# CD40106-4069-Synth.net
KiCad netlist of a schematic drawn in EAGLE
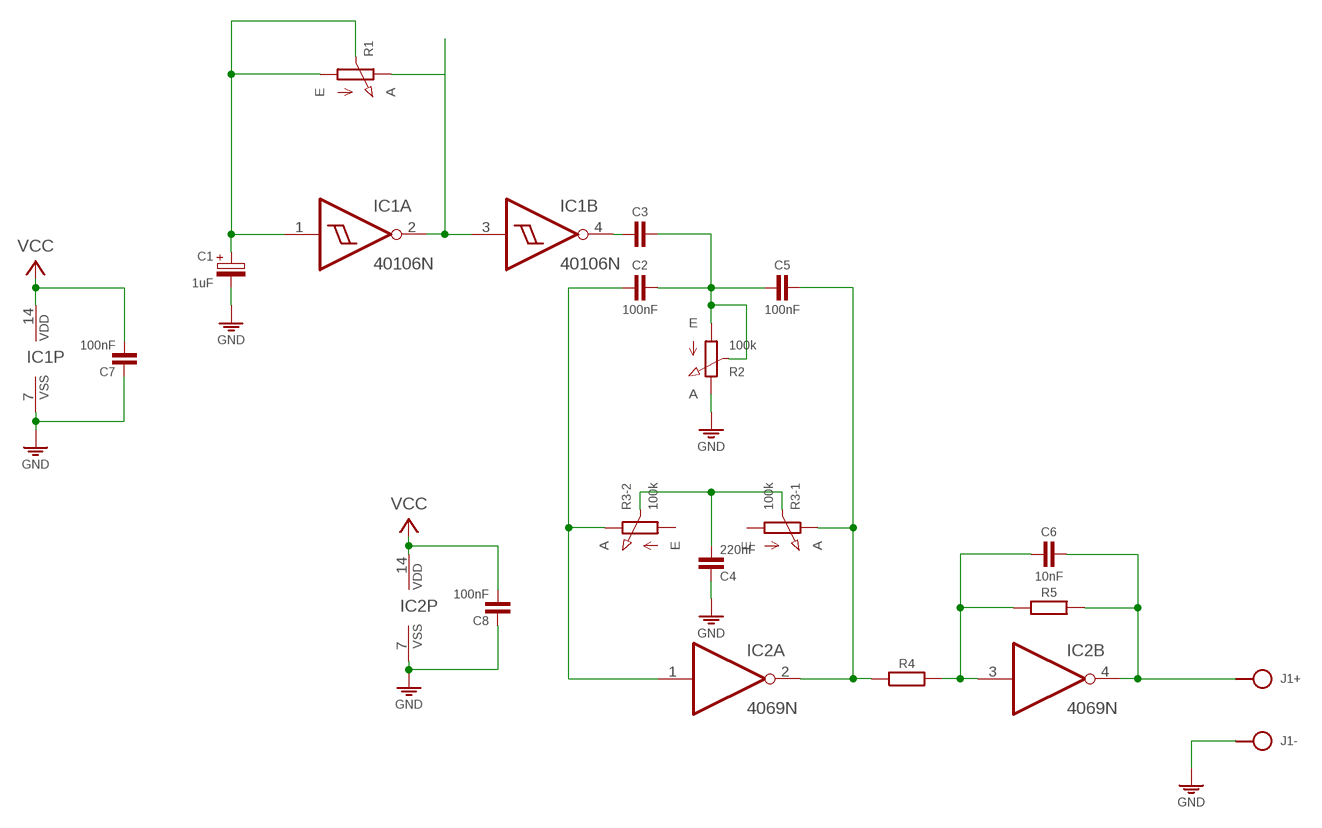
[diagram p0: schematic, sheet 1]

(export (version "E")
  (design (tool "Eeschema 10.0.6"))
  (components
    (comp (ref "C1")
      (value "1uF")
      (footprint "eagle-import:E2.5-4_V")
      (libsource (lib "eagle-import") (part "CPOLE2,5-4/V"))
    )
    (comp (ref "C2")
      (value "100nF")
      (footprint "eagle-import:C050-020X044")
      (libsource (lib "eagle-import") (part "C-H050-020X044"))
    )
    (comp (ref "C3")
      (value "C-H050-020X044")
      (footprint "eagle-import:C050-020X044")
      (libsource (lib "eagle-import") (part "C-H050-020X044"))
    )
    (comp (ref "C4")
      (value "220nF")
      (footprint "eagle-import:C050-020X044_V")
      (libsource (lib "eagle-import") (part "C050-020X044/V"))
    )
    (comp (ref "C5")
      (value "100nF")
      (footprint "eagle-import:C050-020X044")
      (libsource (lib "eagle-import") (part "C-H050-020X044"))
    )
    (comp (ref "C6")
      (value "10nF")
      (footprint "eagle-import:C050-020X044")
      (libsource (lib "eagle-import") (part "C-H050-020X044"))
    )
    (comp (ref "C7")
      (value "100nF")
      (footprint "eagle-import:C050-020X044_V")
      (libsource (lib "eagle-import") (part "C050-020X044/V"))
    )
    (comp (ref "C8")
      (value "100nF")
      (footprint "eagle-import:C050-020X044_V")
      (libsource (lib "eagle-import") (part "C050-020X044/V"))
    )
    (comp (ref "IC1")
      (value "40106N")
      (footprint "eagle-import:DIL14")
      (libsource (lib "eagle-import") (part "40106N"))
    )
    (comp (ref "IC2")
      (value "4069N")
      (footprint "eagle-import:DIL14")
      (libsource (lib "eagle-import") (part "4069N"))
    )
    (comp (ref "J1")
      (value "SPAD+-+-")
      (footprint "eagle-import:SPAD+-")
      (libsource (lib "eagle-import") (part "SPAD+-+-"))
    )
    (comp (ref "J2")
      (value "VCC_GNDL")
      (footprint "eagle-import:SPAD-+")
      (libsource (lib "eagle-import") (part "VCC_GNDL"))
    )
    (comp (ref "R1")
      (value "POT")
      (footprint "eagle-import:POT")
      (libsource (lib "eagle-import") (part "POT"))
    )
    (comp (ref "R2")
      (value "100k")
      (footprint "eagle-import:POT")
      (libsource (lib "eagle-import") (part "POT"))
    )
    (comp (ref "R3")
      (value "100k")
      (footprint "eagle-import:POT-STEREO-2X3")
      (libsource (lib "eagle-import") (part "POT-STEREO"))
    )
    (comp (ref "R4")
      (value "R-H0204/2-V")
      (footprint "eagle-import:0204V")
      (libsource (lib "eagle-import") (part "R-H0204/2-V"))
    )
    (comp (ref "R5")
      (value "R-H0204/10-V")
      (footprint "eagle-import:0204_10-V")
      (libsource (lib "eagle-import") (part "R-H0204/10-V"))
    )
  )
  (nets
    (net (code "1") (name "GND") (class "Default")
      (node (ref "C1") (pin "-") (pinfunction "-_-") (pintype "passive"))
      (node (ref "C4") (pin "1") (pinfunction "1_1") (pintype "passive"))
      (node (ref "C7") (pin "1") (pinfunction "1_1") (pintype "passive"))
      (node (ref "C8") (pin "1") (pinfunction "1_1") (pintype "passive"))
      (node (ref "IC1") (pin "7") (pinfunction "VSS_7") (pintype "power_in"))
      (node (ref "IC2") (pin "7") (pinfunction "VSS_7") (pintype "power_in"))
      (node (ref "J1") (pin "1") (pinfunction "P$1_1") (pintype "passive"))
      (node (ref "J2") (pin "1") (pinfunction "GND_1") (pintype "power_in"))
      (node (ref "R2") (pin "3") (pinfunction "E_3") (pintype "passive"))
    )
    (net (code "2") (name "Net-(IC1A-I)") (class "Default")
      (node (ref "C1") (pin "+") (pinfunction "+_+") (pintype "passive"))
      (node (ref "IC1") (pin "1") (pinfunction "I_1") (pintype "input"))
      (node (ref "R1") (pin "1") (pinfunction "A_1") (pintype "passive"))
      (node (ref "R1") (pin "2") (pinfunction "S_2") (pintype "passive"))
    )
    (net (code "3") (name "Net-(IC1A-O)") (class "Default")
      (node (ref "IC1") (pin "2") (pinfunction "O_2") (pintype "output"))
      (node (ref "IC1") (pin "3") (pinfunction "I_3") (pintype "input"))
      (node (ref "R1") (pin "3") (pinfunction "E_3") (pintype "passive"))
    )
    (net (code "4") (name "Net-(IC1B-O)") (class "Default")
      (node (ref "C3") (pin "1") (pinfunction "1_1") (pintype "passive"))
      (node (ref "IC1") (pin "4") (pinfunction "O_4") (pintype "output"))
    )
    (net (code "5") (name "Net-(IC2A-I)") (class "Default")
      (node (ref "C2") (pin "1") (pinfunction "1_1") (pintype "passive"))
      (node (ref "IC2") (pin "1") (pinfunction "I_1") (pintype "input"))
      (node (ref "R3") (pin "2-E") (pinfunction "E_2-E") (pintype "passive"))
    )
    (net (code "6") (name "Net-(IC2A-O)") (class "Default")
      (node (ref "C5") (pin "2") (pinfunction "2_2") (pintype "passive"))
      (node (ref "IC2") (pin "2") (pinfunction "O_2") (pintype "output"))
      (node (ref "R3") (pin "1-E") (pinfunction "E_1-E") (pintype "passive"))
      (node (ref "R4") (pin "1") (pinfunction "1_1") (pintype "passive"))
    )
    (net (code "7") (name "Net-(IC2B-I)") (class "Default")
      (node (ref "C6") (pin "1") (pinfunction "1_1") (pintype "passive"))
      (node (ref "IC2") (pin "3") (pinfunction "I_3") (pintype "input"))
      (node (ref "R4") (pin "2") (pinfunction "2_2") (pintype "passive"))
      (node (ref "R5") (pin "1") (pinfunction "1_1") (pintype "passive"))
    )
    (net (code "8") (name "Net-(IC2B-O)") (class "Default")
      (node (ref "C6") (pin "2") (pinfunction "2_2") (pintype "passive"))
      (node (ref "IC2") (pin "4") (pinfunction "O_4") (pintype "output"))
      (node (ref "J1") (pin "2") (pinfunction "P$1_2") (pintype "passive"))
      (node (ref "R5") (pin "2") (pinfunction "2_2") (pintype "passive"))
    )
    (net (code "9") (name "Net-(R2-A)") (class "Default")
      (node (ref "C2") (pin "2") (pinfunction "2_2") (pintype "passive"))
      (node (ref "C3") (pin "2") (pinfunction "2_2") (pintype "passive"))
      (node (ref "C5") (pin "1") (pinfunction "1_1") (pintype "passive"))
      (node (ref "R2") (pin "1") (pinfunction "A_1") (pintype "passive"))
      (node (ref "R2") (pin "2") (pinfunction "S_2") (pintype "passive"))
    )
    (net (code "10") (name "Net-(R3A-S)") (class "Default")
      (node (ref "C4") (pin "2") (pinfunction "2_2") (pintype "passive"))
      (node (ref "R3") (pin "1-S") (pinfunction "S_1-S") (pintype "passive"))
      (node (ref "R3") (pin "2-S") (pinfunction "S_2-S") (pintype "passive"))
    )
    (net (code "11") (name "VCC") (class "Default")
      (node (ref "C7") (pin "2") (pinfunction "2_2") (pintype "passive"))
      (node (ref "C8") (pin "2") (pinfunction "2_2") (pintype "passive"))
      (node (ref "IC1") (pin "14") (pinfunction "VDD_14") (pintype "power_in"))
      (node (ref "IC2") (pin "14") (pinfunction "VDD_14") (pintype "power_in"))
      (node (ref "J2") (pin "2") (pinfunction "VCC_2") (pintype "power_in"))
    )
    (net (code "12") (name "unconnected-(R3A-A-Pad1-A)") (class "Default")
      (node (ref "R3") (pin "1-A") (pinfunction "A_1-A") (pintype "passive"))
    )
    (net (code "13") (name "unconnected-(R3B-A-Pad2-A)") (class "Default")
      (node (ref "R3") (pin "2-A") (pinfunction "A_2-A") (pintype "passive"))
    )
  )
)
